# 05_ZYNQ_PS.net
KiCad netlist of a schematic drawn in Altium Designer
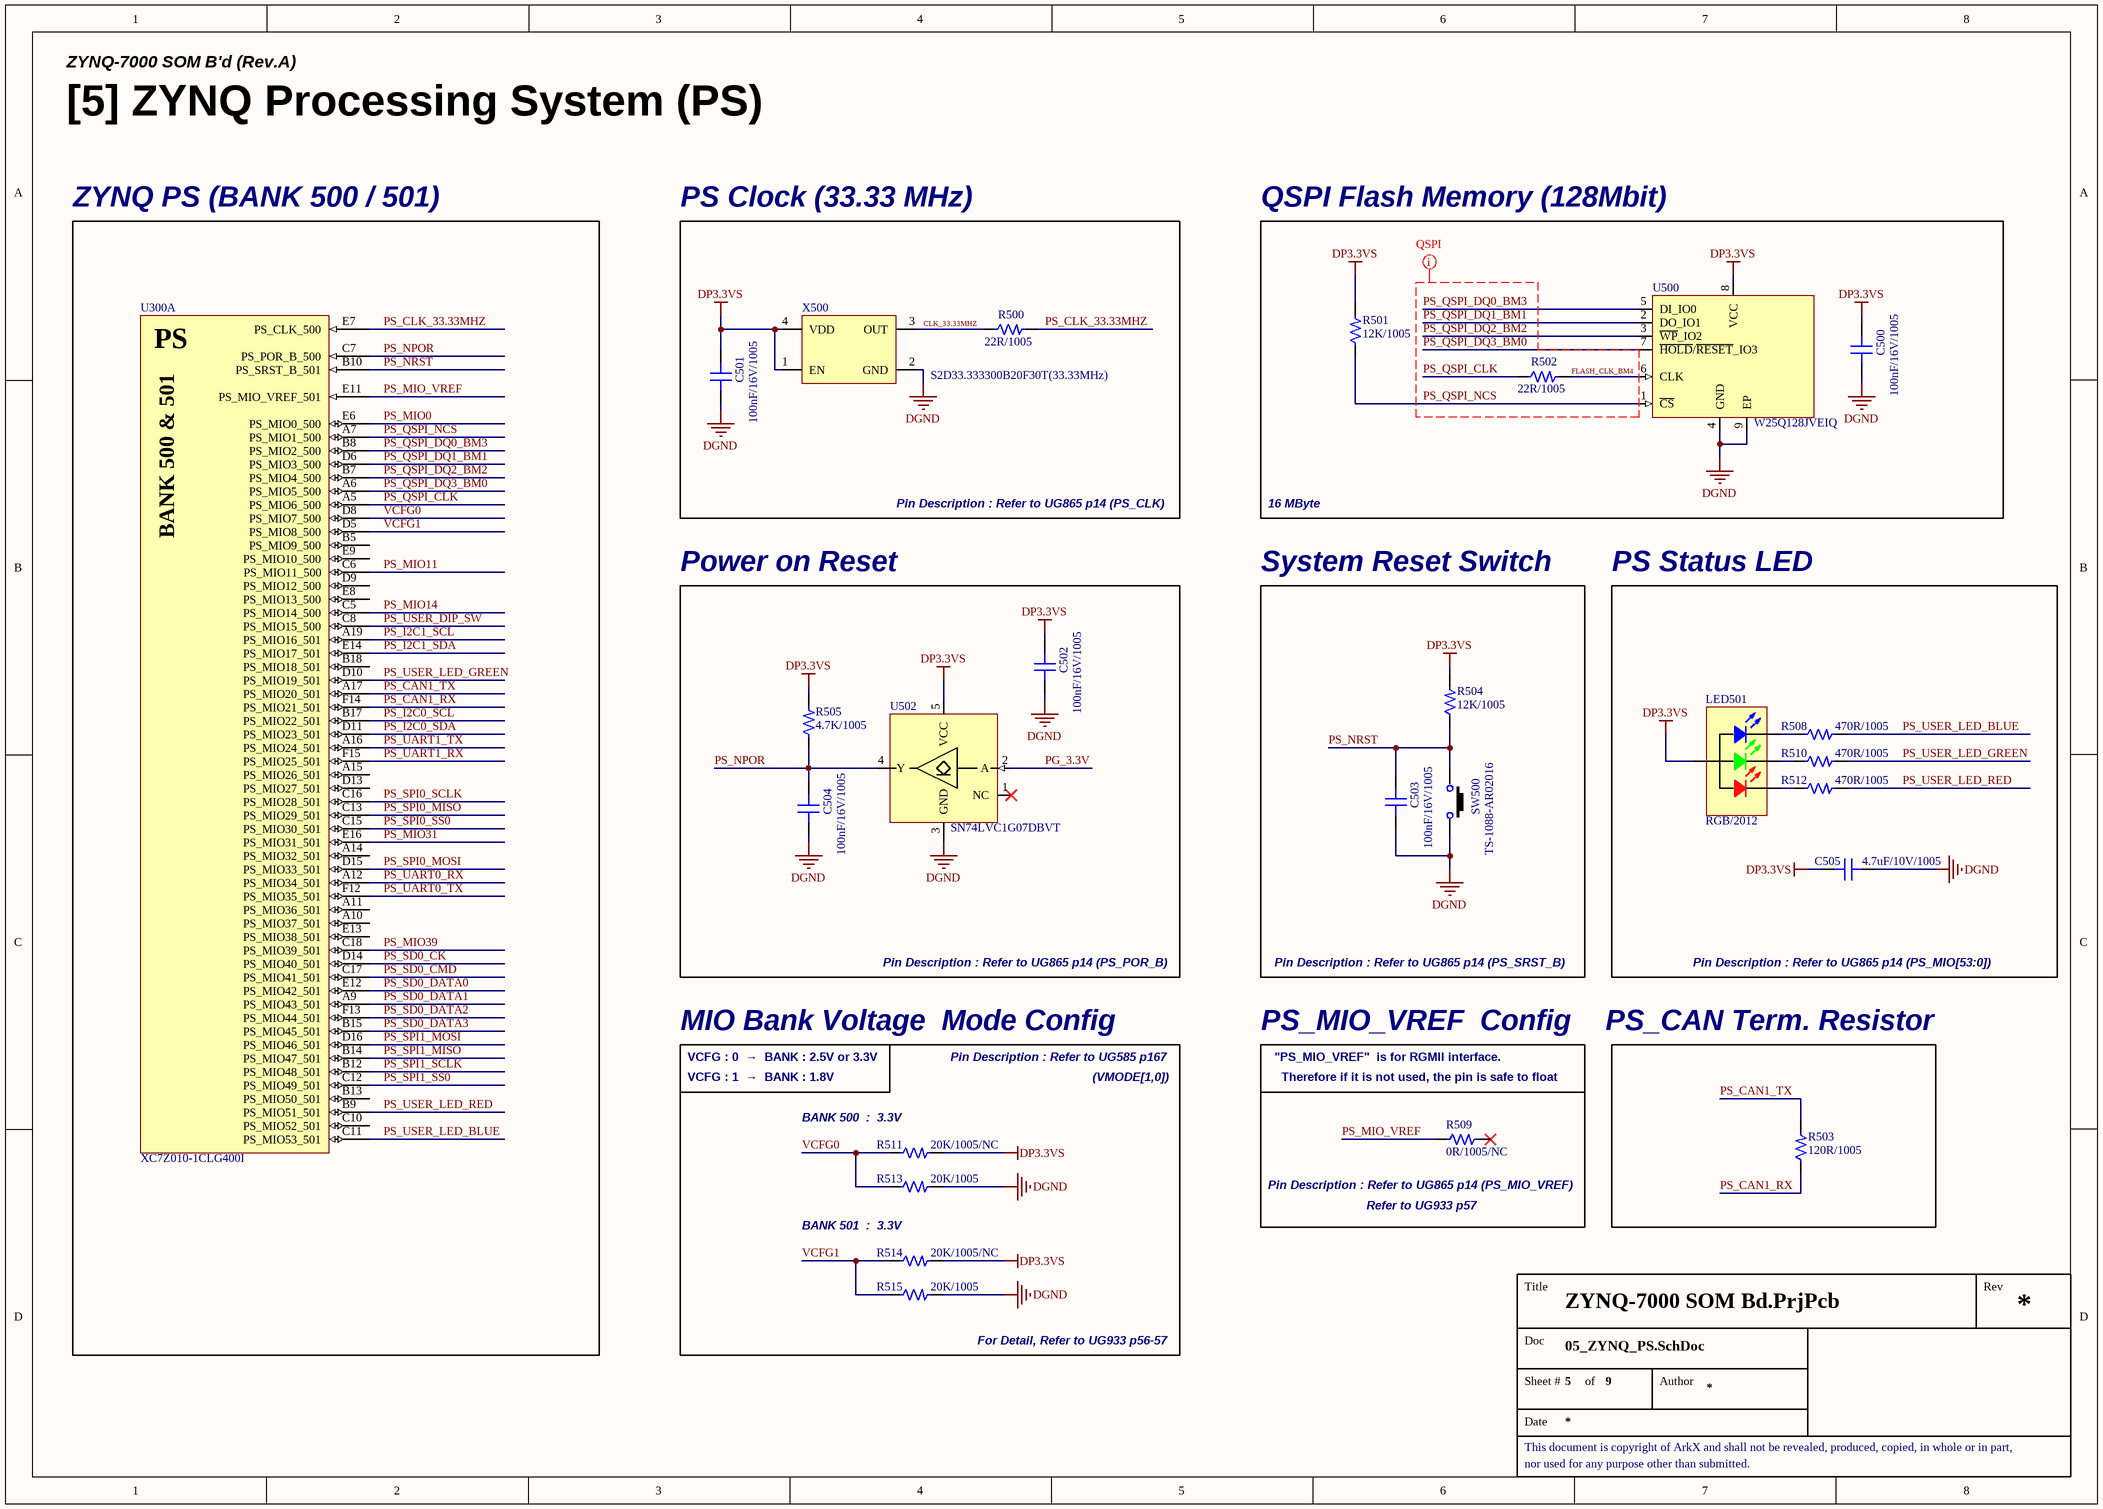
[diagram p0: 05_ZYNQ_PS.SchDoc]

(export (version "E")
  (design (tool "Eeschema 10.0.6"))
  (components
    (comp (ref "C500")
      (value "100nF/16V/1005")
      (footprint "CAP 1005 (0402_INCH)")
      (description "Ceramic CAP_100nF/16V/1005")
      (fields (field (name "LCSC PART #") "C1525"))
      (libsource (lib "Arkx") (part "CAP_100nF/16V/1005"))
    )
    (comp (ref "C501")
      (value "100nF/16V/1005")
      (footprint "CAP 1005 (0402_INCH)")
      (description "Ceramic CAP_100nF/16V/1005")
      (fields (field (name "LCSC PART #") "C1525"))
      (libsource (lib "Arkx") (part "CAP_100nF/16V/1005"))
    )
    (comp (ref "C502")
      (value "100nF/16V/1005")
      (footprint "CAP 1005 (0402_INCH)")
      (description "Ceramic CAP_100nF/16V/1005")
      (fields (field (name "LCSC PART #") "C1525"))
      (libsource (lib "Arkx") (part "CAP_100nF/16V/1005"))
    )
    (comp (ref "C503")
      (value "100nF/16V/1005")
      (footprint "CAP 1005 (0402_INCH)")
      (description "Ceramic CAP_100nF/16V/1005")
      (fields (field (name "LCSC PART #") "C1525"))
      (libsource (lib "Arkx") (part "CAP_100nF/16V/1005"))
    )
    (comp (ref "C504")
      (value "100nF/16V/1005")
      (footprint "CAP 1005 (0402_INCH)")
      (description "Ceramic CAP_100nF/16V/1005")
      (fields (field (name "LCSC PART #") "C1525"))
      (libsource (lib "Arkx") (part "CAP_100nF/16V/1005"))
    )
    (comp (ref "C505")
      (value "4.7uF/10V/1005")
      (footprint "CAP 1005 (0402_INCH)")
      (description "10V 4.7uF X5R ±20% 0402  Multilayer Ceramic Capacitors MLCC - SMD/SMT ROHS")
      (fields (field (name "LCSC PART #") "C23733"))
      (libsource (lib "Arkx") (part "CAP_4.7uF/10V/1005"))
    )
    (comp (ref "LED501")
      (value "RGB/2012")
      (footprint "LED MHT170RGBCT")
      (fields (field (name "LCSC PART #") "C2962094"))
      (libsource (lib "Arkx") (part "LED_RGB_MHT170RGBCT"))
    )
    (comp (ref "R500")
      (value "22R/1005")
      (footprint "RES 1005 (0402_inch)")
      (description "RES_22R/1005/62.5mW")
      (fields (field (name "LCSC PART #") "C25092"))
      (libsource (lib "Arkx") (part "RES_22R/1005/62.5mW"))
    )
    (comp (ref "R501")
      (value "12K/1005")
      (footprint "RES 1005 (0402_inch)")
      (description "RES_12K/1005/62.5mW")
      (fields (field (name "LCSC PART #") "C25752"))
      (libsource (lib "Arkx") (part "RES_12K/1005/62.5mW"))
    )
    (comp (ref "R502")
      (value "22R/1005")
      (footprint "RES 1005 (0402_inch)")
      (description "RES_22R/1005/62.5mW")
      (fields (field (name "LCSC PART #") "C25092"))
      (libsource (lib "Arkx") (part "RES_22R/1005/62.5mW"))
    )
    (comp (ref "R503")
      (value "120R/1005")
      (footprint "RES 1005 (0402_inch)")
      (description "RES_120R/1005/62.5mW")
      (fields (field (name "LCSC PART #") "C25079"))
      (libsource (lib "Arkx") (part "RES_120R/1005/62.5mW"))
    )
    (comp (ref "R504")
      (value "12K/1005")
      (footprint "RES 1005 (0402_inch)")
      (description "RES_12K/1005/62.5mW")
      (fields (field (name "LCSC PART #") "C25752"))
      (libsource (lib "Arkx") (part "RES_12K/1005/62.5mW"))
    )
    (comp (ref "R505")
      (value "4.7K/1005")
      (footprint "RES 1005 (0402_inch)")
      (description "RES_4.7K/1005/62.5mW")
      (fields (field (name "LCSC PART #") "C25900"))
      (libsource (lib "Arkx") (part "RES_4.7K/1005/62.5mW"))
    )
    (comp (ref "R508")
      (value "470R/1005")
      (footprint "RES 1005 (0402_inch)")
      (description "RES_470R/1005/62.5mW")
      (fields (field (name "LCSC PART #") "C25117"))
      (libsource (lib "Arkx") (part "RES_470R/1005/62.5mW"))
    )
    (comp (ref "R509")
      (value "0R/1005/NC")
      (footprint "RES 1005 (0402_inch)/NC")
      (description "RES_0R/1005/62.5mW/NC")
      (libsource (lib "Arkx") (part "RES_NC_0R/1005/62.5mW"))
    )
    (comp (ref "R510")
      (value "470R/1005")
      (footprint "RES 1005 (0402_inch)")
      (description "RES_470R/1005/62.5mW")
      (fields (field (name "LCSC PART #") "C25117"))
      (libsource (lib "Arkx") (part "RES_470R/1005/62.5mW"))
    )
    (comp (ref "R511")
      (value "20K/1005/NC")
      (footprint "RES 1005 (0402_inch)/NC")
      (description "RES_20K/1005/62.5mW/NC")
      (libsource (lib "Arkx") (part "RES_NC_20K/1005/62.5mW"))
    )
    (comp (ref "R512")
      (value "470R/1005")
      (footprint "RES 1005 (0402_inch)")
      (description "RES_470R/1005/62.5mW")
      (fields (field (name "LCSC PART #") "C25117"))
      (libsource (lib "Arkx") (part "RES_470R/1005/62.5mW"))
    )
    (comp (ref "R513")
      (value "20K/1005")
      (footprint "RES 1005 (0402_inch)")
      (description "RES_20K/1005/62.5mW")
      (fields (field (name "LCSC PART #") "C25765"))
      (libsource (lib "Arkx") (part "RES_20K/1005/62.5mW"))
    )
    (comp (ref "R514")
      (value "20K/1005/NC")
      (footprint "RES 1005 (0402_inch)/NC")
      (description "RES_20K/1005/62.5mW/NC")
      (libsource (lib "Arkx") (part "RES_NC_20K/1005/62.5mW"))
    )
    (comp (ref "R515")
      (value "20K/1005")
      (footprint "RES 1005 (0402_inch)")
      (description "RES_20K/1005/62.5mW")
      (fields (field (name "LCSC PART #") "C25765"))
      (libsource (lib "Arkx") (part "RES_20K/1005/62.5mW"))
    )
    (comp (ref "SW500")
      (value "TS-1088-AR02016")
      (footprint "SW_TS-1088-AR02016")
      (description "NO 50mA 100MΩ 100000 Times 12V 160gf@±50gf Brick nogging SPST SMD  Tactile Switches ROHS")
      (fields (field (name "LCSC PART #") "C720477"))
      (libsource (lib "Arkx") (part "SW_TS-1088-AR02016"))
    )
    (comp (ref "U300")
      (value "XC7Z010-1CLG400I")
      (footprint "IC_SOC_XC7Z010-1CLG400I")
      (fields (field (name "LCSC PART #") "C2840994"))
      (libsource (lib "Arkx") (part "IC_SOC_XC7Z010-1CLG400I"))
    )
    (comp (ref "U500")
      (value "W25Q128JVEIQ")
      (footprint "IC_WSON-8-8X6")
      (description "3V 128M-BIT SERIAL FLASH MEMORY WITH DUAL/QUAD SPI & QPI & DTR WSON-8")
      (fields (field (name "MANUFACTURER") "Winbond") (field (name "LCSC PART #") "C401662"))
      (libsource (lib "Arkx") (part "IC_MEM_W25Q128JVEIQ"))
    )
    (comp (ref "U502")
      (value "SN74LVC1G07DBVT")
      (footprint "SOT-23-5 (TI DBV PACKAGE)")
      (description "Single Buffer/Driver With Open-Drain Output / IC BUF NON-INVERT 5.5V SOT23-5")
      (fields (field (name "LCSC PART #") "C2867373"))
      (libsource (lib "Arkx") (part "IC_BUF_SN74LVC1G07DBVT"))
    )
    (comp (ref "X500")
      (value "S2D33.333300B20F30T(33.33MHz)")
      (footprint "OSC SMD_2.5x2.0 (SCTF)")
      (description "3.3V ±20ppm CMOS 33.3333MHz SMD2520-4P  Oscillators ROHS")
      (fields (field (name "LCSC PART #") "C907622"))
      (libsource (lib "Arkx") (part "OSC_S2D33.333300B20F30T(33.33MHz)"))
    )
  )
  (nets
    (net (code "1") (name "/CLK_33.33MHZ") (class "Default")
      (node (ref "R500") (pin "1") (pinfunction "1_1") (pintype "passive"))
      (node (ref "X500") (pin "3") (pinfunction "OUT_3") (pintype "passive"))
    )
    (net (code "2") (name "/FLASH_CLK_BM4") (class "Default")
      (node (ref "R502") (pin "2") (pinfunction "2_2") (pintype "passive"))
      (node (ref "U500") (pin "6") (pinfunction "CLK_6") (pintype "input"))
    )
    (net (code "3") (name "/PG_3.3V") (class "Default")
      (node (ref "U502") (pin "2") (pinfunction "A_2") (pintype "input"))
    )
    (net (code "4") (name "/PS_CAN1_RX") (class "Default")
      (node (ref "R503") (pin "1") (pinfunction "1_1") (pintype "passive"))
      (node (ref "U300") (pin "F14") (pinfunction "PS_MIO21_501_F14") (pintype "bidirectional"))
    )
    (net (code "5") (name "/PS_CAN1_TX") (class "Default")
      (node (ref "R503") (pin "2") (pinfunction "2_2") (pintype "passive"))
      (node (ref "U300") (pin "A17") (pinfunction "PS_MIO20_501_A17") (pintype "bidirectional"))
    )
    (net (code "6") (name "/PS_CLK_33.33MHZ") (class "Default")
      (node (ref "R500") (pin "2") (pinfunction "2_2") (pintype "passive"))
      (node (ref "U300") (pin "E7") (pinfunction "PS_CLK_500_E7") (pintype "input"))
    )
    (net (code "7") (name "/PS_I2C0_SCL") (class "Default")
      (node (ref "U300") (pin "B17") (pinfunction "PS_MIO22_501_B17") (pintype "bidirectional"))
    )
    (net (code "8") (name "/PS_I2C0_SDA") (class "Default")
      (node (ref "U300") (pin "D11") (pinfunction "PS_MIO23_501_D11") (pintype "bidirectional"))
    )
    (net (code "9") (name "/PS_I2C1_SCL") (class "Default")
      (node (ref "U300") (pin "A19") (pinfunction "PS_MIO16_501_A19") (pintype "bidirectional"))
    )
    (net (code "10") (name "/PS_I2C1_SDA") (class "Default")
      (node (ref "U300") (pin "E14") (pinfunction "PS_MIO17_501_E14") (pintype "bidirectional"))
    )
    (net (code "11") (name "/PS_MIO0") (class "Default")
      (node (ref "U300") (pin "E6") (pinfunction "PS_MIO0_500_E6") (pintype "bidirectional"))
    )
    (net (code "12") (name "/PS_MIO11") (class "Default")
      (node (ref "U300") (pin "C6") (pinfunction "PS_MIO11_500_C6") (pintype "bidirectional"))
    )
    (net (code "13") (name "/PS_MIO14") (class "Default")
      (node (ref "U300") (pin "C5") (pinfunction "PS_MIO14_500_C5") (pintype "bidirectional"))
    )
    (net (code "14") (name "/PS_MIO31") (class "Default")
      (node (ref "U300") (pin "E16") (pinfunction "PS_MIO31_501_E16") (pintype "bidirectional"))
    )
    (net (code "15") (name "/PS_MIO39") (class "Default")
      (node (ref "U300") (pin "C18") (pinfunction "PS_MIO39_501_C18") (pintype "bidirectional"))
    )
    (net (code "16") (name "/PS_MIO_VREF") (class "Default")
      (node (ref "R509") (pin "1") (pinfunction "1_1") (pintype "passive"))
      (node (ref "U300") (pin "E11") (pinfunction "PS_MIO_VREF_501_E11") (pintype "input"))
    )
    (net (code "17") (name "/PS_NPOR") (class "Default")
      (node (ref "C504") (pin "1") (pinfunction "1_1") (pintype "passive"))
      (node (ref "R505") (pin "1") (pinfunction "1_1") (pintype "passive"))
      (node (ref "U300") (pin "C7") (pinfunction "PS_POR_B_500_C7") (pintype "input"))
      (node (ref "U502") (pin "4") (pinfunction "Y_4") (pintype "open_collector"))
    )
    (net (code "18") (name "/PS_NRST") (class "Default")
      (node (ref "C503") (pin "1") (pinfunction "1_1") (pintype "passive"))
      (node (ref "R504") (pin "1") (pinfunction "1_1") (pintype "passive"))
      (node (ref "SW500") (pin "1") (pinfunction "1_1") (pintype "passive"))
      (node (ref "U300") (pin "B10") (pinfunction "PS_SRST_B_501_B10") (pintype "input"))
    )
    (net (code "19") (name "/PS_QSPI_CLK") (class "Default")
      (node (ref "R502") (pin "1") (pinfunction "1_1") (pintype "passive"))
      (node (ref "U300") (pin "A5") (pinfunction "PS_MIO6_500_A5") (pintype "bidirectional"))
    )
    (net (code "20") (name "/PS_QSPI_DQ0_BM3") (class "Default")
      (node (ref "U300") (pin "B8") (pinfunction "PS_MIO2_500_B8") (pintype "bidirectional"))
      (node (ref "U500") (pin "5") (pinfunction "DI_IO0_5") (pintype "bidirectional"))
    )
    (net (code "21") (name "/PS_QSPI_DQ1_BM1") (class "Default")
      (node (ref "U300") (pin "D6") (pinfunction "PS_MIO3_500_D6") (pintype "bidirectional"))
      (node (ref "U500") (pin "2") (pinfunction "DO_IO1_2") (pintype "bidirectional"))
    )
    (net (code "22") (name "/PS_QSPI_DQ2_BM2") (class "Default")
      (node (ref "U300") (pin "B7") (pinfunction "PS_MIO4_500_B7") (pintype "bidirectional"))
      (node (ref "U500") (pin "3") (pinfunction "~{WP}_IO2_3") (pintype "bidirectional"))
    )
    (net (code "23") (name "/PS_QSPI_DQ3_BM0") (class "Default")
      (node (ref "U300") (pin "A6") (pinfunction "PS_MIO5_500_A6") (pintype "bidirectional"))
      (node (ref "U500") (pin "7") (pinfunction "~{HOLD}/~{RESET}_IO3_7") (pintype "bidirectional"))
    )
    (net (code "24") (name "/PS_QSPI_NCS") (class "Default")
      (node (ref "R501") (pin "1") (pinfunction "1_1") (pintype "passive"))
      (node (ref "U300") (pin "A7") (pinfunction "PS_MIO1_500_A7") (pintype "bidirectional"))
      (node (ref "U500") (pin "1") (pinfunction "~{CS}_1") (pintype "input"))
    )
    (net (code "25") (name "/PS_SD0_CK") (class "Default")
      (node (ref "U300") (pin "D14") (pinfunction "PS_MIO40_501_D14") (pintype "bidirectional"))
    )
    (net (code "26") (name "/PS_SD0_CMD") (class "Default")
      (node (ref "U300") (pin "C17") (pinfunction "PS_MIO41_501_C17") (pintype "bidirectional"))
    )
    (net (code "27") (name "/PS_SD0_DATA0") (class "Default")
      (node (ref "U300") (pin "E12") (pinfunction "PS_MIO42_501_E12") (pintype "bidirectional"))
    )
    (net (code "28") (name "/PS_SD0_DATA1") (class "Default")
      (node (ref "U300") (pin "A9") (pinfunction "PS_MIO43_501_A9") (pintype "bidirectional"))
    )
    (net (code "29") (name "/PS_SD0_DATA2") (class "Default")
      (node (ref "U300") (pin "F13") (pinfunction "PS_MIO44_501_F13") (pintype "bidirectional"))
    )
    (net (code "30") (name "/PS_SD0_DATA3") (class "Default")
      (node (ref "U300") (pin "B15") (pinfunction "PS_MIO45_501_B15") (pintype "bidirectional"))
    )
    (net (code "31") (name "/PS_SPI0_MISO") (class "Default")
      (node (ref "U300") (pin "C13") (pinfunction "PS_MIO29_501_C13") (pintype "bidirectional"))
    )
    (net (code "32") (name "/PS_SPI0_MOSI") (class "Default")
      (node (ref "U300") (pin "D15") (pinfunction "PS_MIO33_501_D15") (pintype "bidirectional"))
    )
    (net (code "33") (name "/PS_SPI0_SCLK") (class "Default")
      (node (ref "U300") (pin "C16") (pinfunction "PS_MIO28_501_C16") (pintype "bidirectional"))
    )
    (net (code "34") (name "/PS_SPI0_SS0") (class "Default")
      (node (ref "U300") (pin "C15") (pinfunction "PS_MIO30_501_C15") (pintype "bidirectional"))
    )
    (net (code "35") (name "/PS_SPI1_MISO") (class "Default")
      (node (ref "U300") (pin "B14") (pinfunction "PS_MIO47_501_B14") (pintype "bidirectional"))
    )
    (net (code "36") (name "/PS_SPI1_MOSI") (class "Default")
      (node (ref "U300") (pin "D16") (pinfunction "PS_MIO46_501_D16") (pintype "bidirectional"))
    )
    (net (code "37") (name "/PS_SPI1_SCLK") (class "Default")
      (node (ref "U300") (pin "B12") (pinfunction "PS_MIO48_501_B12") (pintype "bidirectional"))
    )
    (net (code "38") (name "/PS_SPI1_SS0") (class "Default")
      (node (ref "U300") (pin "C12") (pinfunction "PS_MIO49_501_C12") (pintype "bidirectional"))
    )
    (net (code "39") (name "/PS_UART0_RX") (class "Default")
      (node (ref "U300") (pin "A12") (pinfunction "PS_MIO34_501_A12") (pintype "bidirectional"))
    )
    (net (code "40") (name "/PS_UART0_TX") (class "Default")
      (node (ref "U300") (pin "F12") (pinfunction "PS_MIO35_501_F12") (pintype "bidirectional"))
    )
    (net (code "41") (name "/PS_UART1_RX") (class "Default")
      (node (ref "U300") (pin "F15") (pinfunction "PS_MIO25_501_F15") (pintype "bidirectional"))
    )
    (net (code "42") (name "/PS_UART1_TX") (class "Default")
      (node (ref "U300") (pin "A16") (pinfunction "PS_MIO24_501_A16") (pintype "bidirectional"))
    )
    (net (code "43") (name "/PS_USER_DIP_SW") (class "Default")
      (node (ref "U300") (pin "C8") (pinfunction "PS_MIO15_500_C8") (pintype "bidirectional"))
    )
    (net (code "44") (name "/PS_USER_LED_BLUE") (class "Default")
      (node (ref "R508") (pin "2") (pinfunction "2_2") (pintype "passive"))
      (node (ref "U300") (pin "C11") (pinfunction "PS_MIO53_501_C11") (pintype "bidirectional"))
    )
    (net (code "45") (name "/PS_USER_LED_GREEN") (class "Default")
      (node (ref "R510") (pin "2") (pinfunction "2_2") (pintype "passive"))
      (node (ref "U300") (pin "D10") (pinfunction "PS_MIO19_501_D10") (pintype "bidirectional"))
    )
    (net (code "46") (name "/PS_USER_LED_RED") (class "Default")
      (node (ref "R512") (pin "2") (pinfunction "2_2") (pintype "passive"))
      (node (ref "U300") (pin "B9") (pinfunction "PS_MIO51_501_B9") (pintype "bidirectional"))
    )
    (net (code "47") (name "/VCFG0") (class "Default")
      (node (ref "R511") (pin "1") (pinfunction "1_1") (pintype "passive"))
      (node (ref "R513") (pin "1") (pinfunction "1_1") (pintype "passive"))
      (node (ref "U300") (pin "D8") (pinfunction "PS_MIO7_500_D8") (pintype "bidirectional"))
    )
    (net (code "48") (name "/VCFG1") (class "Default")
      (node (ref "R514") (pin "1") (pinfunction "1_1") (pintype "passive"))
      (node (ref "R515") (pin "1") (pinfunction "1_1") (pintype "passive"))
      (node (ref "U300") (pin "D5") (pinfunction "PS_MIO8_500_D5") (pintype "bidirectional"))
    )
    (net (code "49") (name "DGND") (class "Default")
      (node (ref "C500") (pin "2") (pinfunction "2_2") (pintype "passive"))
      (node (ref "C501") (pin "2") (pinfunction "2_2") (pintype "passive"))
      (node (ref "C502") (pin "2") (pinfunction "2_2") (pintype "passive"))
      (node (ref "C503") (pin "2") (pinfunction "2_2") (pintype "passive"))
      (node (ref "C504") (pin "2") (pinfunction "2_2") (pintype "passive"))
      (node (ref "C505") (pin "1") (pinfunction "1_1") (pintype "passive"))
      (node (ref "R513") (pin "2") (pinfunction "2_2") (pintype "passive"))
      (node (ref "R515") (pin "2") (pinfunction "2_2") (pintype "passive"))
      (node (ref "SW500") (pin "2") (pinfunction "2_2") (pintype "passive"))
      (node (ref "U500") (pin "4") (pinfunction "GND_4") (pintype "power_in"))
      (node (ref "U500") (pin "9") (pinfunction "EP_9") (pintype "power_in"))
      (node (ref "U502") (pin "3") (pinfunction "GND_3") (pintype "power_in"))
      (node (ref "X500") (pin "2") (pinfunction "GND_2") (pintype "passive"))
    )
    (net (code "50") (name "DP3.3VS") (class "Default")
      (node (ref "C500") (pin "1") (pinfunction "1_1") (pintype "passive"))
      (node (ref "C501") (pin "1") (pinfunction "1_1") (pintype "passive"))
      (node (ref "C502") (pin "1") (pinfunction "1_1") (pintype "passive"))
      (node (ref "C505") (pin "2") (pinfunction "2_2") (pintype "passive"))
      (node (ref "LED501") (pin "4") (pinfunction "Common_Anode_4") (pintype "passive"))
      (node (ref "R501") (pin "2") (pinfunction "2_2") (pintype "passive"))
      (node (ref "R504") (pin "2") (pinfunction "2_2") (pintype "passive"))
      (node (ref "R505") (pin "2") (pinfunction "2_2") (pintype "passive"))
      (node (ref "R511") (pin "2") (pinfunction "2_2") (pintype "passive"))
      (node (ref "R514") (pin "2") (pinfunction "2_2") (pintype "passive"))
      (node (ref "U500") (pin "8") (pinfunction "VCC_8") (pintype "power_in"))
      (node (ref "U502") (pin "5") (pinfunction "VCC_5") (pintype "power_in"))
      (node (ref "X500") (pin "1") (pinfunction "EN_1") (pintype "passive"))
      (node (ref "X500") (pin "4") (pinfunction "VDD_4") (pintype "passive"))
    )
    (net (code "51") (name "Net-(LED501-BLUE)") (class "Default")
      (node (ref "LED501") (pin "3") (pinfunction "BLUE_3") (pintype "passive"))
      (node (ref "R508") (pin "1") (pinfunction "1_1") (pintype "passive"))
    )
    (net (code "52") (name "Net-(LED501-GREEN)") (class "Default")
      (node (ref "LED501") (pin "2") (pinfunction "GREEN_2") (pintype "passive"))
      (node (ref "R510") (pin "1") (pinfunction "1_1") (pintype "passive"))
    )
    (net (code "53") (name "Net-(LED501-RED)") (class "Default")
      (node (ref "LED501") (pin "1") (pinfunction "RED_1") (pintype "passive"))
      (node (ref "R512") (pin "1") (pinfunction "1_1") (pintype "passive"))
    )
    (net (code "54") (name "unconnected-(R509-Pad2)") (class "Default")
      (node (ref "R509") (pin "2") (pinfunction "2_2") (pintype "passive+no_connect"))
    )
    (net (code "55") (name "unconnected-(U300A-PS_MIO9_500-PadB5)") (class "Default")
      (node (ref "U300") (pin "B5") (pinfunction "PS_MIO9_500_B5") (pintype "bidirectional"))
    )
    (net (code "56") (name "unconnected-(U300A-PS_MIO10_500-PadE9)") (class "Default")
      (node (ref "U300") (pin "E9") (pinfunction "PS_MIO10_500_E9") (pintype "bidirectional"))
    )
    (net (code "57") (name "unconnected-(U300A-PS_MIO12_500-PadD9)") (class "Default")
      (node (ref "U300") (pin "D9") (pinfunction "PS_MIO12_500_D9") (pintype "bidirectional"))
    )
    (net (code "58") (name "unconnected-(U300A-PS_MIO13_500-PadE8)") (class "Default")
      (node (ref "U300") (pin "E8") (pinfunction "PS_MIO13_500_E8") (pintype "bidirectional"))
    )
    (net (code "59") (name "unconnected-(U300A-PS_MIO18_501-PadB18)") (class "Default")
      (node (ref "U300") (pin "B18") (pinfunction "PS_MIO18_501_B18") (pintype "bidirectional"))
    )
    (net (code "60") (name "unconnected-(U300A-PS_MIO26_501-PadA15)") (class "Default")
      (node (ref "U300") (pin "A15") (pinfunction "PS_MIO26_501_A15") (pintype "bidirectional"))
    )
    (net (code "61") (name "unconnected-(U300A-PS_MIO27_501-PadD13)") (class "Default")
      (node (ref "U300") (pin "D13") (pinfunction "PS_MIO27_501_D13") (pintype "bidirectional"))
    )
    (net (code "62") (name "unconnected-(U300A-PS_MIO32_501-PadA14)") (class "Default")
      (node (ref "U300") (pin "A14") (pinfunction "PS_MIO32_501_A14") (pintype "bidirectional"))
    )
    (net (code "63") (name "unconnected-(U300A-PS_MIO36_501-PadA11)") (class "Default")
      (node (ref "U300") (pin "A11") (pinfunction "PS_MIO36_501_A11") (pintype "bidirectional"))
    )
    (net (code "64") (name "unconnected-(U300A-PS_MIO37_501-PadA10)") (class "Default")
      (node (ref "U300") (pin "A10") (pinfunction "PS_MIO37_501_A10") (pintype "bidirectional"))
    )
    (net (code "65") (name "unconnected-(U300A-PS_MIO38_501-PadE13)") (class "Default")
      (node (ref "U300") (pin "E13") (pinfunction "PS_MIO38_501_E13") (pintype "bidirectional"))
    )
    (net (code "66") (name "unconnected-(U300A-PS_MIO50_501-PadB13)") (class "Default")
      (node (ref "U300") (pin "B13") (pinfunction "PS_MIO50_501_B13") (pintype "bidirectional"))
    )
    (net (code "67") (name "unconnected-(U300A-PS_MIO52_501-PadC10)") (class "Default")
      (node (ref "U300") (pin "C10") (pinfunction "PS_MIO52_501_C10") (pintype "bidirectional"))
    )
    (net (code "68") (name "unconnected-(U502-NC-Pad1)") (class "Default")
      (node (ref "U502") (pin "1") (pinfunction "NC_1") (pintype "passive+no_connect"))
    )
  )
)
